# APM9328_PS_Reset.net
KiCad netlist of a schematic drawn in Altium Designer
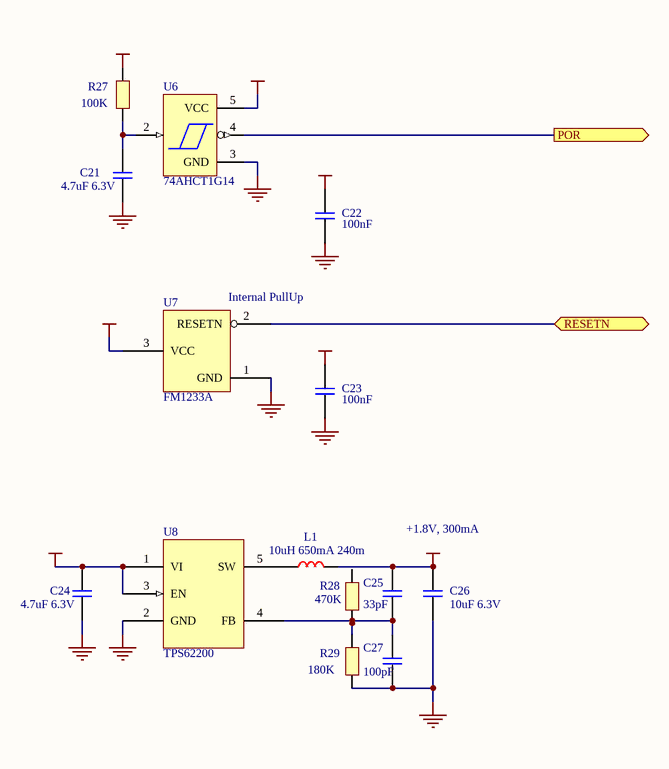
[diagram p0: APM9328_PS_Reset.SchDoc]

(export (version "E")
  (design (tool "Eeschema 10.0.6"))
  (components
    (comp (ref "C21")
      (value "4.7uF 6.3V")
      (footprint "0805")
      (description "Ceramic Capacitor")
      (fields (field (name "MANUFACTURER") "Kemet") (field (name "PART NUMBER") "C0805C475K8PACTU"))
      (libsource (lib "Misc") (part "Cap"))
    )
    (comp (ref "C22") (value "100nF") (footprint "0402") (libsource (lib "Misc") (part "Cap")))
    (comp (ref "C23") (value "100nF") (footprint "0402") (libsource (lib "Misc") (part "Cap")))
    (comp (ref "C24")
      (value "4.7uF 6.3V")
      (footprint "0805")
      (description "Ceramic Capacitor")
      (fields (field (name "MANUFACTURER") "Kemet") (field (name "PART NUMBER") "C0805C475K8PACTU"))
      (libsource (lib "Misc") (part "Cap"))
    )
    (comp (ref "C25") (value "33pF") (footprint "0402") (libsource (lib "Misc") (part "Cap")))
    (comp (ref "C26")
      (value "10uF 6.3V")
      (footprint "0805")
      (description "Ceramic Capacitor")
      (libsource (lib "Misc") (part "Cap"))
    )
    (comp (ref "C27") (value "100pF") (footprint "0402") (libsource (lib "Misc") (part "Cap")))
    (comp (ref "L1")
      (value "10uH 650mA 240m")
      (footprint "Self_1812")
      (description "Self")
      (fields (field (name "MANUFACTURER") "Murata") (field (name "PART NUMBER") "LQH43CN100K03L"))
      (libsource (lib "*") (part "Self"))
    )
    (comp (ref "R27")
      (value "100K")
      (footprint "0402")
      (fields (field (name "MANUFACTURER") "KOA"))
      (libsource (lib "*") (part "Res"))
    )
    (comp (ref "R28") (value "470K") (footprint "0402") (libsource (lib "*") (part "Res")))
    (comp (ref "R29") (value "180K") (footprint "0402") (libsource (lib "*") (part "Res")))
    (comp (ref "U6")
      (value "74AHCT1G14")
      (footprint "SC70-5")
      (description "Single Gate Inverter")
      (fields (field (name "MANUFACTURER") "Texas Instrument") (field (name "PART NUMBER") "SN74AHC1G14DCK"))
      (libsource (lib "*") (part "74AHCT1G14"))
    )
    (comp (ref "U7")
      (value "FM1233A")
      (footprint "SOT23-3")
      (description "Reset IC")
      (fields (field (name "MANUFACTURER") "Fairchild") (field (name "PART NUMBER") "FM1233ACS3X"))
      (libsource (lib "*") (part "FM1233"))
    )
    (comp (ref "U8")
      (value "TPS62200")
      (footprint "SOT23-5")
      (description "High Efficiency DC/DC converter")
      (fields (field (name "MANUFACTURER") "Texas Instrument") (field (name "PART NUMBER") "TPS62200DBV"))
      (libsource (lib "*") (part "TPS62200"))
    )
  )
  (nets
    (net (code "1") (name "+1V8") (class "Default")
      (node (ref "C25") (pin "2") (pintype "passive"))
      (node (ref "C26") (pin "2") (pintype "passive"))
      (node (ref "L1") (pin "2") (pintype "passive"))
    )
    (net (code "2") (name "+3V3") (class "Default")
      (node (ref "C22") (pin "1") (pintype "passive"))
      (node (ref "C23") (pin "1") (pintype "passive"))
      (node (ref "C24") (pin "2") (pintype "passive"))
      (node (ref "R27") (pin "2") (pintype "passive"))
      (node (ref "U6") (pin "5") (pinfunction "VCC_5") (pintype "power_in"))
      (node (ref "U7") (pin "3") (pinfunction "VCC_3") (pintype "power_in"))
      (node (ref "U8") (pin "1") (pinfunction "VI_1") (pintype "power_in"))
      (node (ref "U8") (pin "3") (pinfunction "EN_3") (pintype "input"))
    )
    (net (code "3") (name "/POR") (class "Default") (node (ref "U6") (pin "4") (pintype "output")))
    (net (code "4") (name "/RESETN") (class "Default")
      (node (ref "U7") (pin "2") (pinfunction "RESETN_2") (pintype "open_collector"))
    )
    (net (code "5") (name "GND") (class "Default")
      (node (ref "C21") (pin "1") (pintype "passive"))
      (node (ref "C22") (pin "2") (pintype "passive"))
      (node (ref "C23") (pin "2") (pintype "passive"))
      (node (ref "C24") (pin "1") (pintype "passive"))
      (node (ref "C26") (pin "1") (pintype "passive"))
      (node (ref "C27") (pin "1") (pintype "passive"))
      (node (ref "R29") (pin "1") (pintype "passive"))
      (node (ref "U6") (pin "3") (pinfunction "GND_3") (pintype "power_in"))
      (node (ref "U7") (pin "1") (pinfunction "GND_1") (pintype "power_in"))
      (node (ref "U8") (pin "2") (pinfunction "GND_2") (pintype "power_in"))
    )
    (net (code "6") (name "Net-(C21-Pad2)") (class "Default")
      (node (ref "C21") (pin "2") (pintype "passive"))
      (node (ref "R27") (pin "1") (pintype "passive"))
      (node (ref "U6") (pin "2") (pintype "input"))
    )
    (net (code "7") (name "Net-(U8-FB)") (class "Default")
      (node (ref "C25") (pin "1") (pintype "passive"))
      (node (ref "C27") (pin "2") (pintype "passive"))
      (node (ref "R28") (pin "1") (pintype "passive"))
      (node (ref "R29") (pin "2") (pintype "passive"))
      (node (ref "U8") (pin "4") (pinfunction "FB_4") (pintype "passive"))
    )
    (net (code "8") (name "Net-(U8-SW)") (class "Default")
      (node (ref "L1") (pin "1") (pintype "passive"))
      (node (ref "U8") (pin "5") (pinfunction "SW_5") (pintype "power_in"))
    )
    (net (code "9") (name "unconnected-(R28-Pad2)") (class "Default")
      (node (ref "R28") (pin "2") (pintype "passive"))
    )
    (net (code "10") (name "unconnected-(U6-NC-Pad1)") (class "Default")
      (node (ref "U6") (pin "1") (pinfunction "NC_1") (pintype "passive"))
    )
  )
)
